# v2_0.net
KiCad netlist of a schematic drawn in Altium Designer
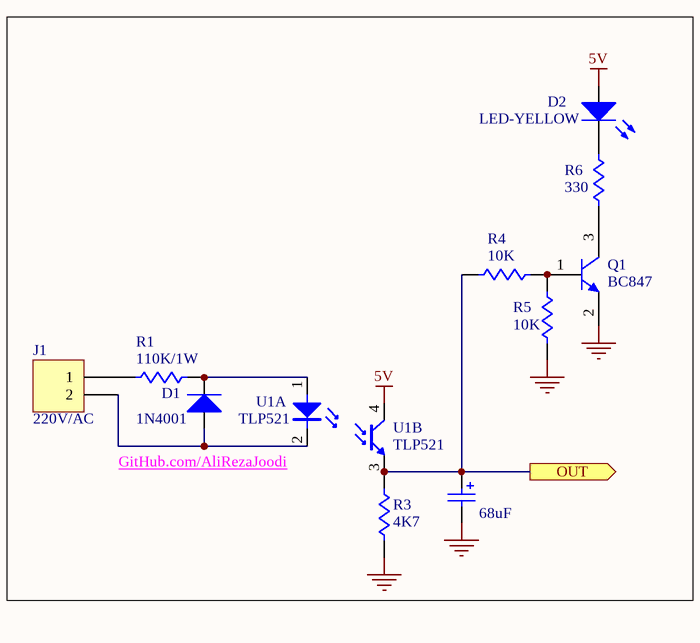
[diagram p0: v2.0.SchDoc]

(export (version "E")
  (design (tool "Eeschema 10.0.6"))
  (components
    (comp (ref "C1")
      (value "68uF")
      (footprint "Cap_D")
      (description "Polarized Capacitor (Radial)")
      (fields
        (field (name "MANUFACTURER") "Generic Components")
        (field (name "Comment") "CAP")
        (field (name "PUBLISHER") "Altium Limited")
      )
      (libsource (lib "Miscellaneous Devices") (part "Cap Pol1"))
    )
    (comp (ref "D1")
      (value "1N4001")
      (footprint "MELF-D3516-1406")
      (description "Default Diode")
      (fields (field (name "MANUFACTURER") "Generic Components") (field (name "PUBLISHER") "Altium Limited"))
      (libsource (lib "Miscellaneous Devices") (part "Diode"))
    )
    (comp (ref "D2")
      (value "LED-YELLOW")
      (footprint "0805_Diode")
      (description "Typical INFRARED GaAs LED")
      (fields (field (name "MANUFACTURER") "Generic Components") (field (name "PUBLISHER") "Altium Limited"))
      (libsource (lib "Miscellaneous Devices") (part "LED"))
    )
    (comp (ref "J1")
      (value "J9")
      (footprint "Fonics_2PIN_1")
      (description "Header, 2-Pin")
      (fields (field (name "PUBLISHER") "Altium Limited"))
      (libsource (lib "Miscellaneous Connectors") (part "Header 2"))
    )
    (comp (ref "Q1")
      (value "BC847")
      (footprint "SOT23-3N")
      (description "Silicon Bipolar Transistor")
      (libsource (lib "my Libraries") (part "BC847"))
    )
    (comp (ref "R1")
      (value "110K/1W")
      (footprint "0805")
      (description "Resistor")
      (fields (field (name "MANUFACTURER") "Generic Components") (field (name "PUBLISHER") "Altium Limited"))
      (libsource (lib "Miscellaneous Devices") (part "Res1"))
    )
    (comp (ref "R3")
      (value "4K7")
      (footprint "0805")
      (description "Resistor")
      (fields (field (name "MANUFACTURER") "Generic Components") (field (name "PUBLISHER") "Altium Limited"))
      (libsource (lib "Miscellaneous Devices") (part "Res1"))
    )
    (comp (ref "R4")
      (value "10K")
      (footprint "0805")
      (description "Resistor")
      (fields (field (name "MANUFACTURER") "Generic Components") (field (name "PUBLISHER") "Altium Limited"))
      (libsource (lib "Miscellaneous Devices") (part "Res1"))
    )
    (comp (ref "R5")
      (value "10K")
      (footprint "0805")
      (description "Resistor")
      (fields (field (name "MANUFACTURER") "Generic Components") (field (name "PUBLISHER") "Altium Limited"))
      (libsource (lib "Miscellaneous Devices") (part "Res1"))
    )
    (comp (ref "R6")
      (value "330")
      (footprint "0805")
      (description "Resistor")
      (fields (field (name "MANUFACTURER") "Generic Components") (field (name "PUBLISHER") "Altium Limited"))
      (libsource (lib "Miscellaneous Devices") (part "Res1"))
    )
    (comp (ref "U1")
      (value "TLP521")
      (footprint "SMD_4PIN")
      (fields (field (name "PUBLISHER") "Altium Limited"))
      (libsource (lib "my Libraries") (part "Optoisolator"))
    )
  )
  (nets
    (net (code "1") (name "/OUT") (class "Default")
      (node (ref "C1") (pin "1") (pinfunction "1_1") (pintype "passive"))
      (node (ref "R3") (pin "1") (pinfunction "1_1") (pintype "passive"))
      (node (ref "R4") (pin "1") (pinfunction "1_1") (pintype "passive"))
      (node (ref "U1") (pin "3") (pinfunction "E_3") (pintype "passive"))
    )
    (net (code "2") (name "5V") (class "Default")
      (node (ref "D2") (pin "1") (pinfunction "A_1") (pintype "passive"))
      (node (ref "U1") (pin "4") (pinfunction "C_4") (pintype "passive"))
    )
    (net (code "3") (name "GND") (class "Default")
      (node (ref "C1") (pin "2") (pinfunction "2_2") (pintype "passive"))
      (node (ref "Q1") (pin "2") (pinfunction "E_2") (pintype "passive"))
      (node (ref "R3") (pin "2") (pinfunction "2_2") (pintype "passive"))
      (node (ref "R5") (pin "1") (pinfunction "1_1") (pintype "passive"))
    )
    (net (code "4") (name "Net-(D1-A)") (class "Default")
      (node (ref "D1") (pin "1") (pinfunction "A_1") (pintype "passive"))
      (node (ref "J1") (pin "2") (pinfunction "2_2") (pintype "passive"))
      (node (ref "U1") (pin "2") (pinfunction "K_2") (pintype "power_in"))
    )
    (net (code "5") (name "Net-(D1-K)") (class "Default")
      (node (ref "D1") (pin "2") (pinfunction "K_2") (pintype "passive"))
      (node (ref "R1") (pin "2") (pinfunction "2_2") (pintype "passive"))
      (node (ref "U1") (pin "1") (pinfunction "A_1") (pintype "power_in"))
    )
    (net (code "6") (name "Net-(D2-K)") (class "Default")
      (node (ref "D2") (pin "2") (pinfunction "K_2") (pintype "passive"))
      (node (ref "R6") (pin "1") (pinfunction "1_1") (pintype "passive"))
    )
    (net (code "7") (name "Net-(J1-Pad1)") (class "Default")
      (node (ref "J1") (pin "1") (pinfunction "1_1") (pintype "passive"))
      (node (ref "R1") (pin "1") (pinfunction "1_1") (pintype "passive"))
    )
    (net (code "8") (name "Net-(Q1-B)") (class "Default")
      (node (ref "Q1") (pin "1") (pinfunction "B_1") (pintype "passive"))
      (node (ref "R4") (pin "2") (pinfunction "2_2") (pintype "passive"))
      (node (ref "R5") (pin "2") (pinfunction "2_2") (pintype "passive"))
    )
    (net (code "9") (name "Net-(Q1-C)") (class "Default")
      (node (ref "Q1") (pin "3") (pinfunction "C_3") (pintype "passive"))
      (node (ref "R6") (pin "2") (pinfunction "2_2") (pintype "passive"))
    )
  )
)
